# RF-Test-Board-Sch.net
KiCad netlist of a schematic drawn in Altium Designer
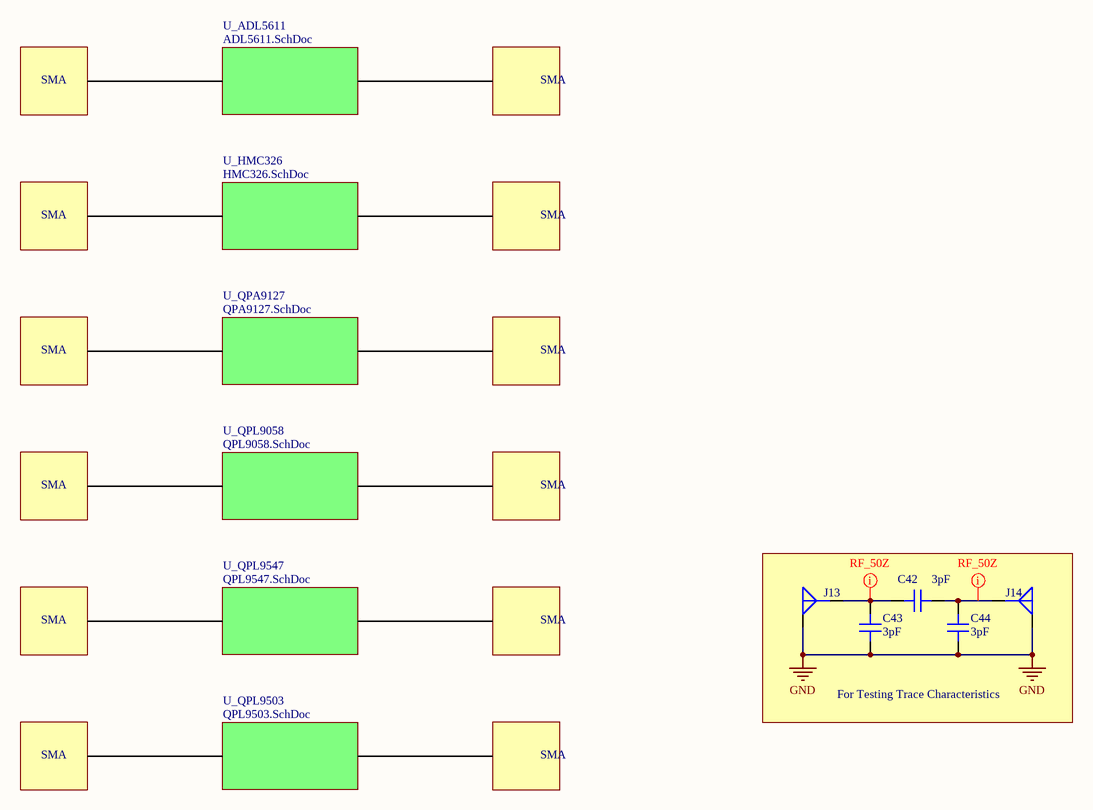
[diagram p0: RF-Test-Board-Sch.SchDoc]

(export (version "E")
  (design (tool "Eeschema 10.0.6"))
  (components
    (comp (ref "C42")
      (value "3pF")
      (footprint "CAP 0402_1005 RF")
      (description "CAP CER 3PF 50V C0G/NP0 0402")
      (fields
        (field (name "PART NUMBER") "GJM1555C1H3R0CB01J")
        (field (name "MANUFACTURER") "Murata Electronics")
      )
      (libsource (lib "Celestial Altium Library - altium_library") (part "Capacitor"))
    )
    (comp (ref "C43")
      (value "3pF")
      (footprint "CAP 0402_1005 RF")
      (description "CAP CER 3PF 50V C0G/NP0 0402")
      (fields
        (field (name "PART NUMBER") "GJM1555C1H3R0CB01J")
        (field (name "MANUFACTURER") "Murata Electronics")
      )
      (libsource (lib "Celestial Altium Library - altium_library") (part "Capacitor"))
    )
    (comp (ref "C44")
      (value "3pF")
      (footprint "CAP 0402_1005 RF")
      (description "CAP CER 3PF 50V C0G/NP0 0402")
      (fields
        (field (name "PART NUMBER") "GJM1555C1H3R0CB01J")
        (field (name "MANUFACTURER") "Murata Electronics")
      )
      (libsource (lib "Celestial Altium Library - altium_library") (part "Capacitor"))
    )
    (comp (ref "J13")
      (value "CON-SMA-EDGE-S")
      (footprint "CON-SMA-EDGE-S")
      (description "CONN SMA JACK STR EDGE MNT")
      (libsource (lib "Connector") (part "CON-SMA-EDGE-S"))
    )
    (comp (ref "J14")
      (value "CON-SMA-EDGE-S")
      (footprint "CON-SMA-EDGE-S")
      (description "CONN SMA JACK STR EDGE MNT")
      (libsource (lib "Connector") (part "CON-SMA-EDGE-S"))
    )
  )
  (nets
    (net (code "1") (name "GND") (class "Default")
      (node (ref "C43") (pin "1") (pinfunction "1_1") (pintype "passive"))
      (node (ref "C44") (pin "1") (pinfunction "1_1") (pintype "passive"))
      (node (ref "J13") (pin "2") (pinfunction "G_2") (pintype "passive"))
      (node (ref "J14") (pin "2") (pinfunction "G_2") (pintype "passive"))
    )
    (net (code "2") (name "Net-(J13-S)") (class "Default")
      (node (ref "C42") (pin "2") (pinfunction "2_2") (pintype "passive"))
      (node (ref "C43") (pin "2") (pinfunction "2_2") (pintype "passive"))
      (node (ref "J13") (pin "1") (pinfunction "S_1") (pintype "passive"))
    )
    (net (code "3") (name "Net-(J14-S)") (class "Default")
      (node (ref "C42") (pin "1") (pinfunction "1_1") (pintype "passive"))
      (node (ref "C44") (pin "2") (pinfunction "2_2") (pintype "passive"))
      (node (ref "J14") (pin "1") (pinfunction "S_1") (pintype "passive"))
    )
  )
)
